# 1s.net
KiCad netlist of a schematic drawn in EAGLE
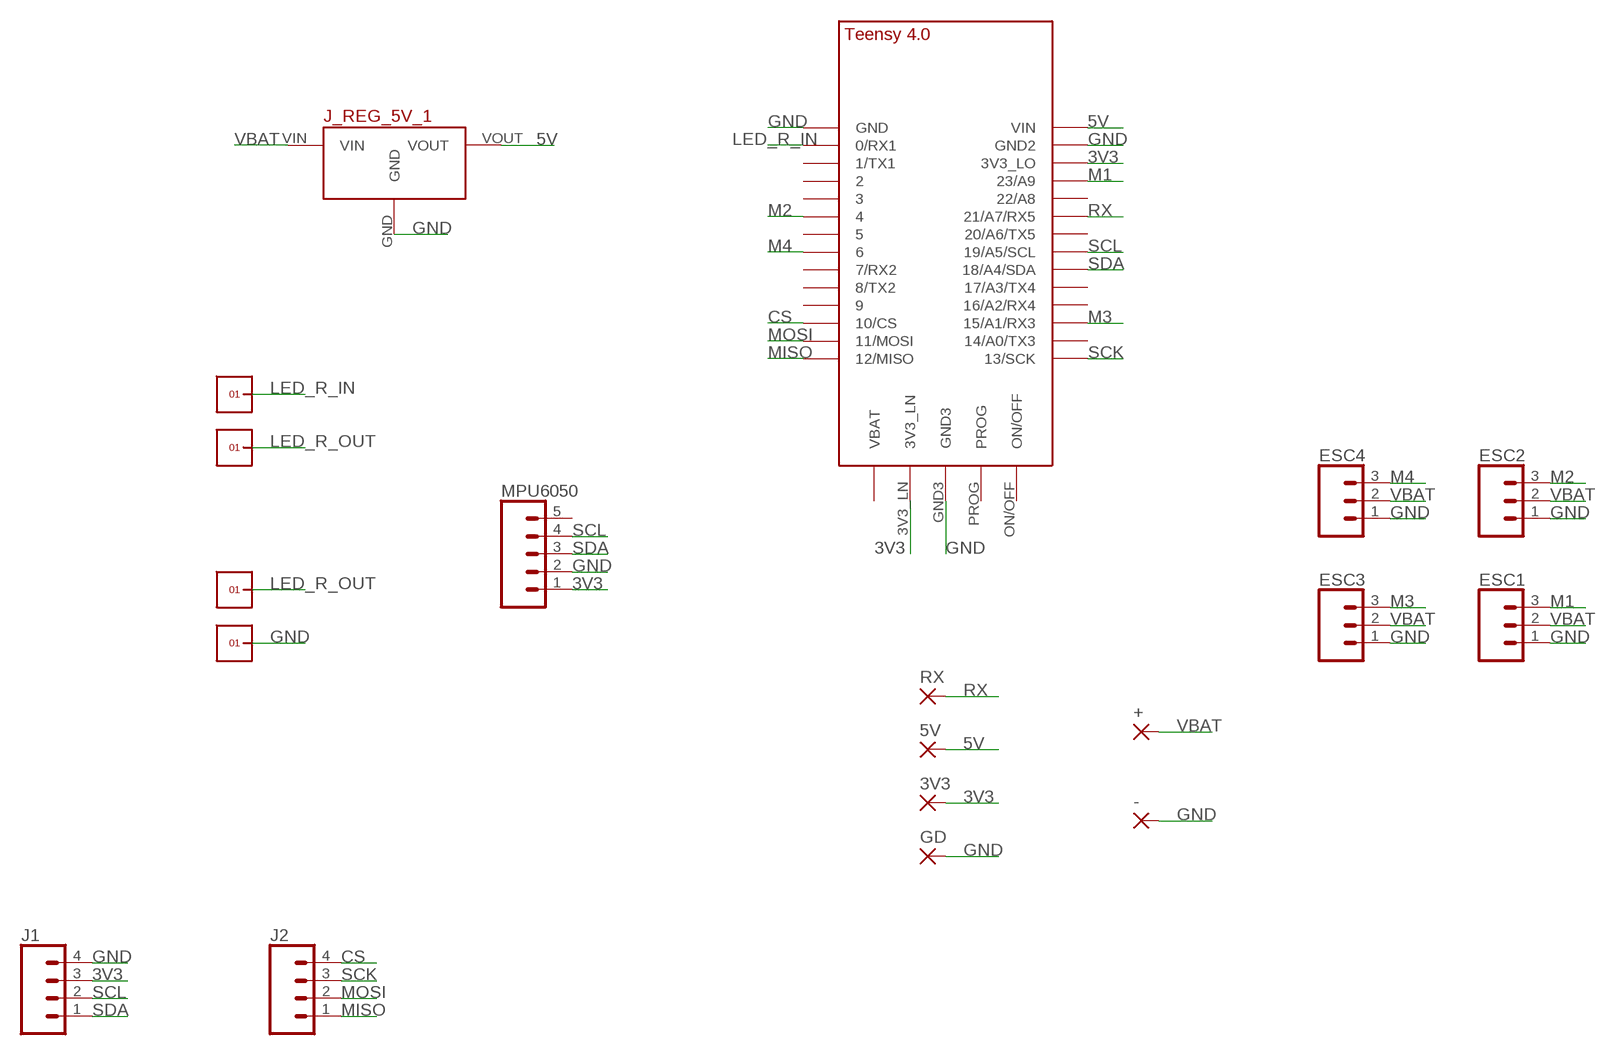
[diagram p0: schematic, sheet 1]

(export (version "E")
  (design (tool "Eeschema 10.0.6"))
  (components
    (comp (ref "+")
      (value "SMD5")
      (footprint "eagle-import:SMD2,54-5,08")
      (libsource (lib "eagle-import") (part "SMD5"))
    )
    (comp (ref "-")
      (value "SMD5")
      (footprint "eagle-import:SMD2,54-5,08")
      (libsource (lib "eagle-import") (part "SMD5"))
    )
    (comp (ref "3V3")
      (value "SMD2")
      (footprint "eagle-import:SMD1,27-2,54")
      (libsource (lib "eagle-import") (part "SMD2"))
    )
    (comp (ref "5V")
      (value "SMD2")
      (footprint "eagle-import:SMD1,27-2,54")
      (libsource (lib "eagle-import") (part "SMD2"))
    )
    (comp (ref "ESC1")
      (value "455-1750-1-ND")
      (footprint "eagle-import:1X03")
      (libsource (lib "eagle-import") (part "CONN_03"))
    )
    (comp (ref "ESC2")
      (value "455-1750-1-ND")
      (footprint "eagle-import:1X03")
      (libsource (lib "eagle-import") (part "CONN_03"))
    )
    (comp (ref "ESC3")
      (value "455-1750-1-ND")
      (footprint "eagle-import:1X03")
      (libsource (lib "eagle-import") (part "CONN_03"))
    )
    (comp (ref "ESC4")
      (value "455-1750-1-ND")
      (footprint "eagle-import:1X03")
      (libsource (lib "eagle-import") (part "CONN_03"))
    )
    (comp (ref "GD")
      (value "SMD2")
      (footprint "eagle-import:SMD1,27-2,54")
      (libsource (lib "eagle-import") (part "SMD2"))
    )
    (comp (ref "J1")
      (value "CONN_041X04_NO_SILK")
      (footprint "eagle-import:1X04_NO_SILK")
      (libsource (lib "eagle-import") (part "CONN_041X04_NO_SILK"))
    )
    (comp (ref "J2")
      (value "CONN_041X04_NO_SILK")
      (footprint "eagle-import:1X04_NO_SILK")
      (libsource (lib "eagle-import") (part "CONN_041X04_NO_SILK"))
    )
    (comp (ref "J_REG_5V_1")
      (value "5V_VOLTAGE_REGULATOR")
      (footprint "eagle-import:5V_VOLTAGE_REGULATOR")
      (libsource (lib "eagle-import") (part "5V_VOLTAGE_REGULATOR"))
    )
    (comp (ref "MPU6050")
      (value "CONN_05NO_SILK")
      (footprint "eagle-import:1X05_NO_SILK")
      (libsource (lib "eagle-import") (part "CONN_05NO_SILK"))
    )
    (comp (ref "RX")
      (value "SMD2")
      (footprint "eagle-import:SMD1,27-2,54")
      (libsource (lib "eagle-import") (part "SMD2"))
    )
    (comp (ref "U$1")
      (value "TEENSY_4.0")
      (footprint "eagle-import:TEENSY_4.0")
      (libsource (lib "eagle-import") (part "TEENSY_4.0"))
    )
    (comp (ref "U$3")
      (value "1X1")
      (footprint "eagle-import:1X1")
      (libsource (lib "eagle-import") (part "1X1"))
    )
    (comp (ref "U$4")
      (value "1X1")
      (footprint "eagle-import:1X1")
      (libsource (lib "eagle-import") (part "1X1"))
    )
    (comp (ref "U$6")
      (value "1X1")
      (footprint "eagle-import:1X1")
      (libsource (lib "eagle-import") (part "1X1"))
    )
    (comp (ref "U$7")
      (value "1X1")
      (footprint "eagle-import:1X1")
      (libsource (lib "eagle-import") (part "1X1"))
    )
  )
  (nets
    (net (code "1") (name "/3V3") (class "Default")
      (node (ref "3V3") (pin "1") (pinfunction "P_1") (pintype "passive"))
      (node (ref "J1") (pin "3") (pinfunction "3_3") (pintype "passive"))
      (node (ref "MPU6050") (pin "1") (pinfunction "1_1") (pintype "passive"))
      (node (ref "U$1") (pin "3V3_LN") (pinfunction "3V3_LN_3V3_LN") (pintype "bidirectional"))
      (node (ref "U$1") (pin "3V3_LO") (pinfunction "3V3_LO_3V3_LO") (pintype "bidirectional"))
    )
    (net (code "2") (name "/5V") (class "Default")
      (node (ref "5V") (pin "1") (pinfunction "P_1") (pintype "passive"))
      (node (ref "J_REG_5V_1") (pin "VOUT") (pinfunction "VOUT_VOUT") (pintype "bidirectional"))
      (node (ref "U$1") (pin "VIN") (pinfunction "VIN_VIN") (pintype "bidirectional"))
    )
    (net (code "3") (name "/CS") (class "Default")
      (node (ref "J2") (pin "4") (pinfunction "4_4") (pintype "passive"))
      (node (ref "U$1") (pin "10/CS") (pinfunction "10/CS_10/CS") (pintype "bidirectional"))
    )
    (net (code "4") (name "/GND") (class "Default")
      (node (ref "-") (pin "1") (pinfunction "P_1") (pintype "passive"))
      (node (ref "ESC1") (pin "1") (pinfunction "1_1") (pintype "passive"))
      (node (ref "ESC2") (pin "1") (pinfunction "1_1") (pintype "passive"))
      (node (ref "ESC3") (pin "1") (pinfunction "1_1") (pintype "passive"))
      (node (ref "ESC4") (pin "1") (pinfunction "1_1") (pintype "passive"))
      (node (ref "GD") (pin "1") (pinfunction "P_1") (pintype "passive"))
      (node (ref "J1") (pin "4") (pinfunction "4_4") (pintype "passive"))
      (node (ref "J_REG_5V_1") (pin "GND") (pinfunction "GND_GND") (pintype "bidirectional"))
      (node (ref "MPU6050") (pin "2") (pinfunction "2_2") (pintype "passive"))
      (node (ref "U$1") (pin "GND") (pinfunction "GND_GND") (pintype "bidirectional"))
      (node (ref "U$1") (pin "GND2") (pinfunction "GND2_GND2") (pintype "bidirectional"))
      (node (ref "U$1") (pin "GND3") (pinfunction "GND3_GND3") (pintype "bidirectional"))
      (node (ref "U$7") (pin "1") (pinfunction "1_1") (pintype "bidirectional"))
    )
    (net (code "5") (name "/LED_R_IN") (class "Default")
      (node (ref "U$1") (pin "0/RX") (pinfunction "0/RX1_0/RX") (pintype "bidirectional"))
      (node (ref "U$3") (pin "1") (pinfunction "1_1") (pintype "bidirectional"))
    )
    (net (code "6") (name "/LED_R_OUT") (class "Default")
      (node (ref "U$4") (pin "1") (pinfunction "1_1") (pintype "bidirectional"))
      (node (ref "U$6") (pin "1") (pinfunction "1_1") (pintype "bidirectional"))
    )
    (net (code "7") (name "/M1") (class "Default")
      (node (ref "ESC1") (pin "3") (pinfunction "3_3") (pintype "passive"))
      (node (ref "U$1") (pin "23/A9") (pinfunction "23/A9_23/A9") (pintype "bidirectional"))
    )
    (net (code "8") (name "/M2") (class "Default")
      (node (ref "ESC2") (pin "3") (pinfunction "3_3") (pintype "passive"))
      (node (ref "U$1") (pin "4/CANRX") (pinfunction "4_4/CANRX") (pintype "bidirectional"))
    )
    (net (code "9") (name "/M3") (class "Default")
      (node (ref "ESC3") (pin "3") (pinfunction "3_3") (pintype "passive"))
      (node (ref "U$1") (pin "15/A1") (pinfunction "15/A1/RX3_15/A1") (pintype "bidirectional"))
    )
    (net (code "10") (name "/M4") (class "Default")
      (node (ref "ESC4") (pin "3") (pinfunction "3_3") (pintype "passive"))
      (node (ref "U$1") (pin "6") (pinfunction "6_6") (pintype "bidirectional"))
    )
    (net (code "11") (name "/MISO") (class "Default")
      (node (ref "J2") (pin "1") (pinfunction "1_1") (pintype "passive"))
      (node (ref "U$1") (pin "12/MISO") (pinfunction "12/MISO_12/MISO") (pintype "bidirectional"))
    )
    (net (code "12") (name "/MOSI") (class "Default")
      (node (ref "J2") (pin "2") (pinfunction "2_2") (pintype "passive"))
      (node (ref "U$1") (pin "11/MOSI") (pinfunction "11/MOSI_11/MOSI") (pintype "bidirectional"))
    )
    (net (code "13") (name "/RX") (class "Default")
      (node (ref "RX") (pin "1") (pinfunction "P_1") (pintype "passive"))
      (node (ref "U$1") (pin "21/A7") (pinfunction "21/A7/RX5_21/A7") (pintype "bidirectional"))
    )
    (net (code "14") (name "/SCK") (class "Default")
      (node (ref "J2") (pin "3") (pinfunction "3_3") (pintype "passive"))
      (node (ref "U$1") (pin "13/SCK") (pinfunction "13/SCK_13/SCK") (pintype "bidirectional"))
    )
    (net (code "15") (name "/SCL") (class "Default")
      (node (ref "J1") (pin "2") (pinfunction "2_2") (pintype "passive"))
      (node (ref "MPU6050") (pin "4") (pinfunction "4_4") (pintype "passive"))
      (node (ref "U$1") (pin "19/A5/SCL") (pinfunction "19/A5/SCL_19/A5/SCL") (pintype "bidirectional"))
    )
    (net (code "16") (name "/SDA") (class "Default")
      (node (ref "J1") (pin "1") (pinfunction "1_1") (pintype "passive"))
      (node (ref "MPU6050") (pin "3") (pinfunction "3_3") (pintype "passive"))
      (node (ref "U$1") (pin "18/A4/SDA") (pinfunction "18/A4/SDA_18/A4/SDA") (pintype "bidirectional"))
    )
    (net (code "17") (name "/VBAT") (class "Default")
      (node (ref "+") (pin "1") (pinfunction "P_1") (pintype "passive"))
      (node (ref "ESC1") (pin "2") (pinfunction "2_2") (pintype "passive"))
      (node (ref "ESC2") (pin "2") (pinfunction "2_2") (pintype "passive"))
      (node (ref "ESC3") (pin "2") (pinfunction "2_2") (pintype "passive"))
      (node (ref "ESC4") (pin "2") (pinfunction "2_2") (pintype "passive"))
      (node (ref "J_REG_5V_1") (pin "VIN") (pinfunction "VIN_VIN") (pintype "bidirectional"))
    )
    (net (code "18") (name "unconnected-(MPU6050-Pad5)") (class "Default")
      (node (ref "MPU6050") (pin "5") (pinfunction "5_5") (pintype "passive"))
    )
    (net (code "19") (name "unconnected-(U$1-1{slash}TX1-Pad1{slash}TX)") (class "Default")
      (node (ref "U$1") (pin "1/TX") (pinfunction "1/TX1_1/TX") (pintype "bidirectional"))
    )
    (net (code "20") (name "unconnected-(U$1-3-Pad3{slash}CANTX)") (class "Default")
      (node (ref "U$1") (pin "3/CANTX") (pinfunction "3_3/CANTX") (pintype "bidirectional"))
    )
    (net (code "21") (name "unconnected-(U$1-7{slash}RX2-Pad7)") (class "Default")
      (node (ref "U$1") (pin "7") (pinfunction "7/RX2_7") (pintype "bidirectional"))
    )
    (net (code "22") (name "unconnected-(U$1-8{slash}TX2-Pad8)") (class "Default")
      (node (ref "U$1") (pin "8") (pinfunction "8/TX2_8") (pintype "bidirectional"))
    )
    (net (code "23") (name "unconnected-(U$1-9-Pad9{slash}CS)") (class "Default")
      (node (ref "U$1") (pin "9/CS") (pinfunction "9_9/CS") (pintype "bidirectional"))
    )
    (net (code "24") (name "unconnected-(U$1-14{slash}A0{slash}TX3-Pad14{slash}A0)") (class "Default")
      (node (ref "U$1") (pin "14/A0") (pinfunction "14/A0/TX3_14/A0") (pintype "bidirectional"))
    )
    (net (code "25") (name "unconnected-(U$1-16{slash}A2{slash}RX4-Pad16{slash}A2)") (class "Default")
      (node (ref "U$1") (pin "16/A2") (pinfunction "16/A2/RX4_16/A2") (pintype "bidirectional"))
    )
    (net (code "26") (name "unconnected-(U$1-17{slash}A3{slash}TX4-Pad17{slash}A3)") (class "Default")
      (node (ref "U$1") (pin "17/A3") (pinfunction "17/A3/TX4_17/A3") (pintype "bidirectional"))
    )
    (net (code "27") (name "unconnected-(U$1-20{slash}A6{slash}TX5-Pad20{slash}A6)") (class "Default")
      (node (ref "U$1") (pin "20/A6") (pinfunction "20/A6/TX5_20/A6") (pintype "bidirectional"))
    )
    (net (code "28") (name "unconnected-(U$1-Pad2)") (class "Default")
      (node (ref "U$1") (pin "2") (pinfunction "2_2") (pintype "bidirectional"))
    )
    (net (code "29") (name "unconnected-(U$1-Pad5)") (class "Default")
      (node (ref "U$1") (pin "5") (pinfunction "5_5") (pintype "bidirectional"))
    )
    (net (code "30") (name "unconnected-(U$1-Pad22{slash}A8)") (class "Default")
      (node (ref "U$1") (pin "22/A8") (pinfunction "22/A8_22/A8") (pintype "bidirectional"))
    )
    (net (code "31") (name "unconnected-(U$1-PadON{slash}OFF)") (class "Default")
      (node (ref "U$1") (pin "ON/OFF") (pinfunction "ON/OFF_ON/OFF") (pintype "bidirectional"))
    )
    (net (code "32") (name "unconnected-(U$1-PadPROG)") (class "Default")
      (node (ref "U$1") (pin "PROG") (pinfunction "PROG_PROG") (pintype "bidirectional"))
    )
    (net (code "33") (name "unconnected-(U$1-VBAT-PadVBAT\\)") (class "Default")
      (node (ref "U$1") (pin "VBAT\\") (pinfunction "VBAT_VBAT\\") (pintype "bidirectional"))
    )
  )
)
